# tweeq-extMod_I2C_Adapter_v2.net
KiCad netlist of a schematic drawn in EAGLE
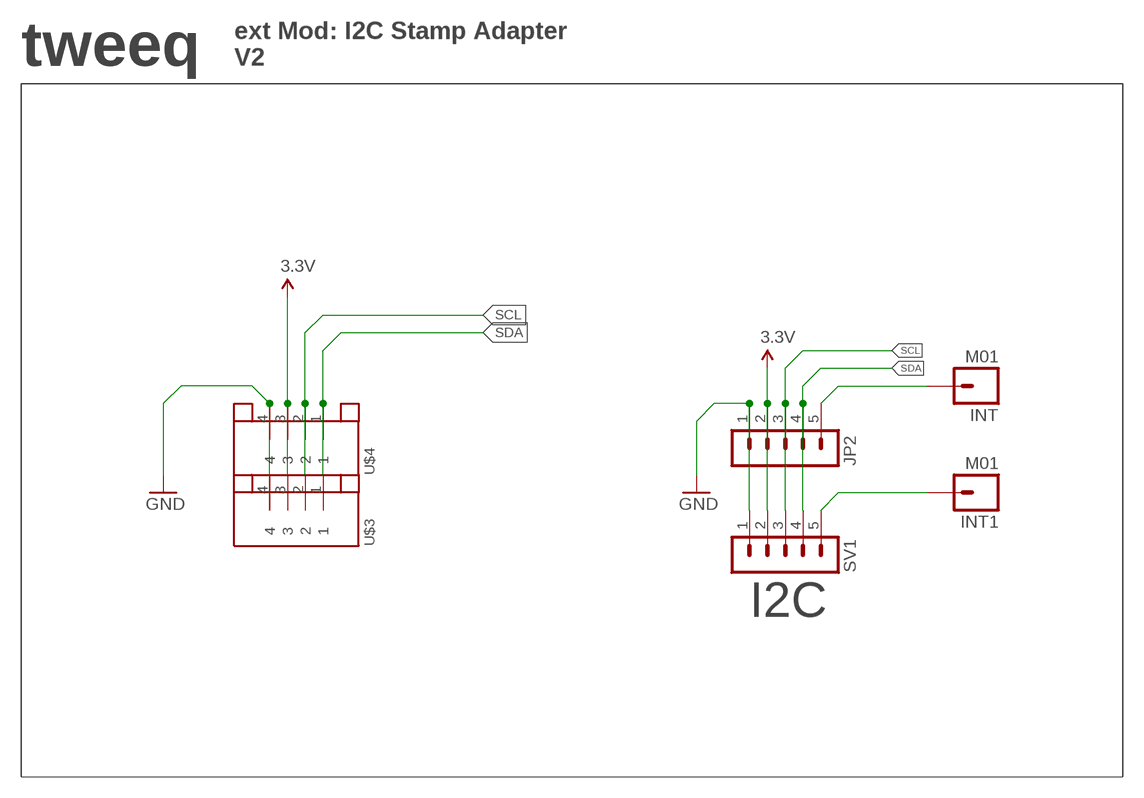
[diagram p0: schematic, sheet 1]

(export (version "E")
  (design (tool "Eeschema 10.0.6"))
  (components
    (comp (ref "INT")
      (value "M01")
      (footprint "eagle-import:AISCUBE_1X01_TIGHTFITVIA")
      (libsource (lib "eagle-import") (part "M01"))
    )
    (comp (ref "INT1")
      (value "M01")
      (footprint "eagle-import:AISCUBE_1X01_TIGHTFITVIA")
      (libsource (lib "eagle-import") (part "M01"))
    )
    (comp (ref "JP2")
      (value "M05-11.5MM-SMT")
      (footprint "eagle-import:1X05-1.5MM-SMT")
      (libsource (lib "eagle-import") (part "M05-11.5MM-SMT"))
    )
    (comp (ref "SV1")
      (value "M05-11.5MM-SMT")
      (footprint "eagle-import:1X05-1.5MM-SMT")
      (libsource (lib "eagle-import") (part "M05-11.5MM-SMT"))
    )
    (comp (ref "U$3")
      (value "JST-4PINSH")
      (footprint "eagle-import:SH1.0-4PIN")
      (libsource (lib "eagle-import") (part "JST-4PINSH"))
    )
    (comp (ref "U$4")
      (value "JST-4PINSH")
      (footprint "eagle-import:SH1.0-4PIN")
      (libsource (lib "eagle-import") (part "JST-4PINSH"))
    )
  )
  (nets
    (net (code "1") (name "3.3V") (class "Default")
      (node (ref "JP2") (pin "2") (pinfunction "2_2") (pintype "passive"))
      (node (ref "SV1") (pin "2") (pinfunction "2_2") (pintype "passive"))
      (node (ref "U$3") (pin "3") (pinfunction "3_3") (pintype "bidirectional"))
      (node (ref "U$4") (pin "3") (pinfunction "3_3") (pintype "bidirectional"))
    )
    (net (code "2") (name "GND") (class "Default")
      (node (ref "JP2") (pin "1") (pinfunction "1_1") (pintype "passive"))
      (node (ref "SV1") (pin "1") (pinfunction "1_1") (pintype "passive"))
      (node (ref "U$4") (pin "4") (pinfunction "4_4") (pintype "bidirectional"))
    )
    (net (code "3") (name "Net-(INT-1)") (class "Default")
      (node (ref "INT") (pin "P$1") (pinfunction "1_P$1") (pintype "passive"))
      (node (ref "JP2") (pin "5") (pinfunction "5_5") (pintype "passive"))
    )
    (net (code "4") (name "Net-(INT1-1)") (class "Default")
      (node (ref "INT1") (pin "P$1") (pinfunction "1_P$1") (pintype "passive"))
      (node (ref "SV1") (pin "5") (pinfunction "5_5") (pintype "passive"))
    )
    (net (code "5") (name "SCL") (class "Default")
      (node (ref "JP2") (pin "3") (pinfunction "3_3") (pintype "passive"))
      (node (ref "SV1") (pin "3") (pinfunction "3_3") (pintype "passive"))
      (node (ref "U$3") (pin "2") (pinfunction "2_2") (pintype "bidirectional"))
      (node (ref "U$4") (pin "2") (pinfunction "2_2") (pintype "bidirectional"))
    )
    (net (code "6") (name "SDA") (class "Default")
      (node (ref "JP2") (pin "4") (pinfunction "4_4") (pintype "passive"))
      (node (ref "SV1") (pin "4") (pinfunction "4_4") (pintype "passive"))
      (node (ref "U$3") (pin "1") (pinfunction "1_1") (pintype "bidirectional"))
      (node (ref "U$4") (pin "1") (pinfunction "1_1") (pintype "bidirectional"))
    )
    (net (code "7") (name "unconnected-(U$3-Pad4)") (class "Default")
      (node (ref "U$3") (pin "4") (pinfunction "4_4") (pintype "bidirectional"))
    )
  )
)
